# Power_Distribution_-_Rear_Camera_and_Cha.net
KiCad netlist of a schematic drawn in Altium Designer
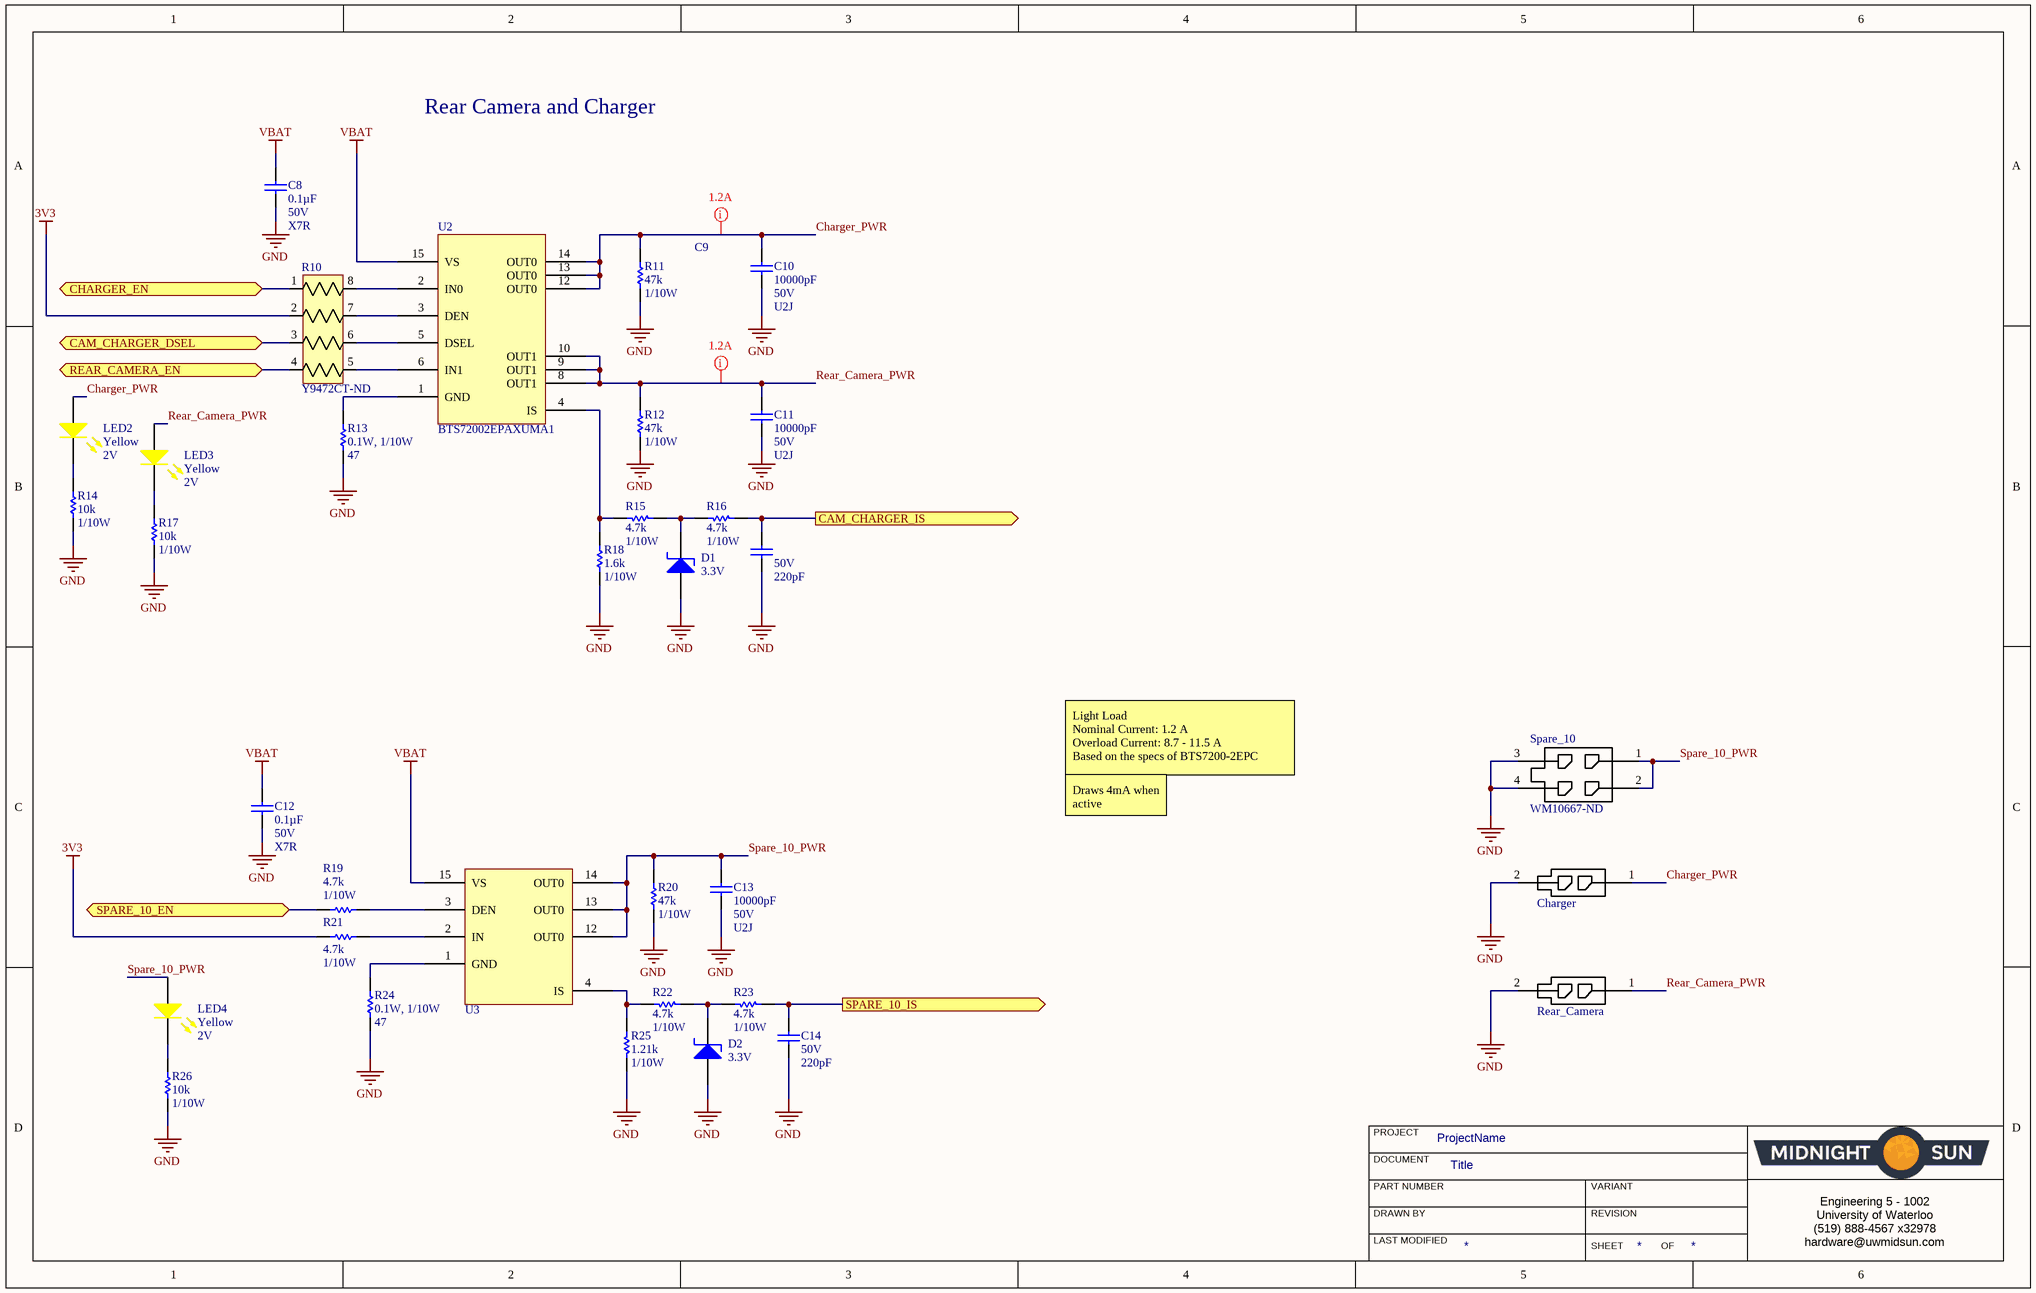
[diagram p0: Power Distribution -  Rear Camera and Charger.SchDoc]

(export (version "E")
  (design (tool "Eeschema 10.0.6"))
  (components
    (comp (ref "C8")
      (value "CAP CER 0.1UF 50V 10% X7R 0603")
      (footprint "CAP, 0603")
      (description "0.10µF ±10% 50V Ceramic Capacitor X7R 0603 (1608 Metric)")
      (fields
        (field (name "TOLERANCE") "±10%")
        (field (name "CAPACITANCE") "0.1µF")
        (field (name "VOLTAGE") "50V")
        (field (name "TEMPERATURE COEFFICIENT") "X7R")
      )
      (libsource (lib "Schematic Diagrams") (part "CAP CER 0.1UF 50V 10% X7R 0603"))
    )
    (comp (ref "C9")
      (value "CAP CER 220PF 50V C0G/NP0 0603")
      (footprint "CAP, 0603")
      (description "220pF ±5% 50V Ceramic Capacitor C0G, NP0 0603 (1608 Metric)")
      (fields
        (field (name "MANUFACTURER") "KEMET")
        (field (name "TOLERANCE") "5%")
        (field (name "VOLTAGE RATING") "50V")
        (field (name "CAPACITANCE") "220pF")
      )
      (libsource (lib "Schematic Diagrams") (part "CAP CER 220PF 50V C0G/NP0 0603"))
    )
    (comp (ref "C10")
      (value "CAP CER 10nF 50V 5% X7R 0603")
      (footprint "CAP, 0603")
      (description "10000pF ±5% 50V Ceramic Capacitor U2J 0603 (1608 Metric)")
      (fields
        (field (name "TOLERANCE") "±5%")
        (field (name "CAPACITANCE") "10000pF")
        (field (name "VOLTAGE") "50V")
        (field (name "TEMPERATURE COEFFICIENT") "U2J")
      )
      (libsource (lib "Schematic Diagrams") (part "CAP CER 10nF 50V 5% X7R 0603"))
    )
    (comp (ref "C11")
      (value "CAP CER 10nF 50V 5% X7R 0603")
      (footprint "CAP, 0603")
      (description "10000pF ±5% 50V Ceramic Capacitor U2J 0603 (1608 Metric)")
      (fields
        (field (name "TOLERANCE") "±5%")
        (field (name "CAPACITANCE") "10000pF")
        (field (name "VOLTAGE") "50V")
        (field (name "TEMPERATURE COEFFICIENT") "U2J")
      )
      (libsource (lib "Schematic Diagrams") (part "CAP CER 10nF 50V 5% X7R 0603"))
    )
    (comp (ref "C12")
      (value "CAP CER 0.1UF 50V 10% X7R 0603")
      (footprint "CAP, 0603")
      (description "0.10µF ±10% 50V Ceramic Capacitor X7R 0603 (1608 Metric)")
      (fields
        (field (name "TOLERANCE") "±10%")
        (field (name "CAPACITANCE") "0.1µF")
        (field (name "VOLTAGE") "50V")
        (field (name "TEMPERATURE COEFFICIENT") "X7R")
      )
      (libsource (lib "Schematic Diagrams") (part "CAP CER 0.1UF 50V 10% X7R 0603"))
    )
    (comp (ref "C13")
      (value "CAP CER 10nF 50V 5% X7R 0603")
      (footprint "CAP, 0603")
      (description "10000pF ±5% 50V Ceramic Capacitor U2J 0603 (1608 Metric)")
      (fields
        (field (name "TOLERANCE") "±5%")
        (field (name "CAPACITANCE") "10000pF")
        (field (name "VOLTAGE") "50V")
        (field (name "TEMPERATURE COEFFICIENT") "U2J")
      )
      (libsource (lib "Schematic Diagrams") (part "CAP CER 10nF 50V 5% X7R 0603"))
    )
    (comp (ref "C14")
      (value "CAP CER 220PF 50V C0G/NP0 0603")
      (footprint "CAP, 0603")
      (description "220pF ±5% 50V Ceramic Capacitor C0G, NP0 0603 (1608 Metric)")
      (fields
        (field (name "MANUFACTURER") "KEMET")
        (field (name "TOLERANCE") "5%")
        (field (name "VOLTAGE RATING") "50V")
        (field (name "CAPACITANCE") "220pF")
      )
      (libsource (lib "Schematic Diagrams") (part "CAP CER 220PF 50V C0G/NP0 0603"))
    )
    (comp (ref "Charger")
      (value "CONN 2POS MICRO-FIT 3mm")
      (footprint "CONN, 2POS MICRO-FIT")
      (description "Connector Header Through Hole 2 position")
      (fields (field (name "MANUFACTURER") "Molex") (field (name "MANUFACTURER PART NUMBER") "43045-0227"))
      (libsource (lib "Schematic Diagrams") (part "CONN 2POS MICRO-FIT 3mm"))
    )
    (comp (ref "D1")
      (value "DIODE ZENER 3.3V 200MW SOD323")
      (footprint "sod-323")
      (description "Zener Diode 3.3V 200mW ±5% Surface Mount SOD-323")
      (fields (field (name "VOLTAGE") "3.3V"))
      (libsource (lib "Schematic Diagrams") (part "DIODE ZENER 3.3V 200MW SOD323"))
    )
    (comp (ref "D2")
      (value "DIODE ZENER 3.3V 200MW SOD323")
      (footprint "sod-323")
      (description "Zener Diode 3.3V 200mW ±5% Surface Mount SOD-323")
      (fields (field (name "VOLTAGE") "3.3V"))
      (libsource (lib "Schematic Diagrams") (part "DIODE ZENER 3.3V 200MW SOD323"))
    )
    (comp (ref "LED2")
      (value "LED YELLOW CLEAR 2.1V 0603")
      (footprint "LED_0603")
      (description "Yellow 590nm LED Indication - Discrete 2V 0603 (1608 Metric)")
      (fields
        (field (name "MANUFACTURER") "Wurth Electronics Inc.")
        (field (name "MANUFACTURER PART NUMBER") "150060YS75000")
        (field (name "COLOR") "Yellow")
        (field (name "VOLTAGE - FORWARD (VF) (TYP)") "2V")
      )
      (libsource (lib "Schematic Diagrams") (part "LED YELLOW CLEAR 2.1V 0603"))
    )
    (comp (ref "LED3")
      (value "LED YELLOW CLEAR 2.1V 0603")
      (footprint "LED_0603")
      (description "Yellow 590nm LED Indication - Discrete 2V 0603 (1608 Metric)")
      (fields
        (field (name "MANUFACTURER") "Wurth Electronics Inc.")
        (field (name "MANUFACTURER PART NUMBER") "150060YS75000")
        (field (name "COLOR") "Yellow")
        (field (name "VOLTAGE - FORWARD (VF) (TYP)") "2V")
      )
      (libsource (lib "Schematic Diagrams") (part "LED YELLOW CLEAR 2.1V 0603"))
    )
    (comp (ref "LED4")
      (value "LED YELLOW CLEAR 2.1V 0603")
      (footprint "LED_0603")
      (description "Yellow 590nm LED Indication - Discrete 2V 0603 (1608 Metric)")
      (fields
        (field (name "MANUFACTURER") "Wurth Electronics Inc.")
        (field (name "MANUFACTURER PART NUMBER") "150060YS75000")
        (field (name "COLOR") "Yellow")
        (field (name "VOLTAGE - FORWARD (VF) (TYP)") "2V")
      )
      (libsource (lib "Schematic Diagrams") (part "LED YELLOW CLEAR 2.1V 0603"))
    )
    (comp (ref "R10")
      (value "RES ARRAY 4 RES 4.7K OHM 1206")
      (footprint "RES ARRAY 4RES 1206")
      (fields (field (name "TOLERANCE") "±5%") (field (name "SUPPLIER PART NUMBER 1") "Y9472CT-ND"))
      (libsource (lib "Schematic Diagrams") (part "RES ARRAY 4 RES 4.7K OHM 1206"))
    )
    (comp (ref "R11")
      (value "RES 47K OHM 1% 1/10W 0603")
      (footprint "RES, 0603")
      (description "47 kOhms ±1% 0.1W, 1/10W Chip Resistor 0603 (1608 Metric) Automotive AEC-Q200 Thick Film")
      (fields
        (field (name "MANUFACTURER") "Panasonic")
        (field (name "MANUFACTURER PART NUMBER") "ERJ3EKF4702V")
        (field (name "RESISTANCE") "47k")
        (field (name "POWER RATING") "1/10W")
      )
      (libsource (lib "Schematic Diagrams") (part "RES 47K OHM 1% 1/10W 0603"))
    )
    (comp (ref "R12")
      (value "RES 47K OHM 1% 1/10W 0603")
      (footprint "RES, 0603")
      (description "47 kOhms ±1% 0.1W, 1/10W Chip Resistor 0603 (1608 Metric) Automotive AEC-Q200 Thick Film")
      (fields
        (field (name "MANUFACTURER") "Panasonic")
        (field (name "MANUFACTURER PART NUMBER") "ERJ3EKF4702V")
        (field (name "RESISTANCE") "47k")
        (field (name "POWER RATING") "1/10W")
      )
      (libsource (lib "Schematic Diagrams") (part "RES 47K OHM 1% 1/10W 0603"))
    )
    (comp (ref "R13")
      (value "RES SMD 47 OHM 1% 1/10W 0603")
      (footprint "RES, 0603")
      (fields
        (field (name "TOLERANCE") "±1%")
        (field (name "POWER (WATTS)") "0.1W, 1/10W")
        (field (name "VALUES") "47")
      )
      (libsource (lib "Schematic Diagrams") (part "RES SMD 47 OHM 1% 1/10W 0603"))
    )
    (comp (ref "R14")
      (value "RES 10K OHM 1% 1/10W 0603")
      (footprint "RES, 0603")
      (description "RES SMD 10K OHM 1% 1/10W 0603")
      (fields
        (field (name "TOLERANCE") "±1%")
        (field (name "RESISTANCE") "10k")
        (field (name "POWER") "1/10W")
      )
      (libsource (lib "Schematic Diagrams") (part "RES 10K OHM 1% 1/10W 0603"))
    )
    (comp (ref "R15")
      (value "RES 4.7K OHM 1% 1/10W 0603")
      (footprint "RES, 0603")
      (description "4.7k Ohm ±1% 0.1W, 1/10W Chip Resistor 0603 (1608 Metric) Moisture Resistant Thick Film")
      (fields
        (field (name "TOLERANCE") "±1%")
        (field (name "RESISTANCE (OHMS)") "4.7k")
        (field (name "POWER (WATTS)") "1/10W")
      )
      (libsource (lib "Schematic Diagrams") (part "RES 4.7K OHM 1% 1/10W 0603"))
    )
    (comp (ref "R16")
      (value "RES 4.7K OHM 1% 1/10W 0603")
      (footprint "RES, 0603")
      (description "4.7k Ohm ±1% 0.1W, 1/10W Chip Resistor 0603 (1608 Metric) Moisture Resistant Thick Film")
      (fields
        (field (name "TOLERANCE") "±1%")
        (field (name "RESISTANCE (OHMS)") "4.7k")
        (field (name "POWER (WATTS)") "1/10W")
      )
      (libsource (lib "Schematic Diagrams") (part "RES 4.7K OHM 1% 1/10W 0603"))
    )
    (comp (ref "R17")
      (value "RES 10K OHM 1% 1/10W 0603")
      (footprint "RES, 0603")
      (description "RES SMD 10K OHM 1% 1/10W 0603")
      (fields
        (field (name "TOLERANCE") "±1%")
        (field (name "RESISTANCE") "10k")
        (field (name "POWER") "1/10W")
      )
      (libsource (lib "Schematic Diagrams") (part "RES 10K OHM 1% 1/10W 0603"))
    )
    (comp (ref "R18")
      (value "RES 1.6K OHM 1% 1/10W 0603")
      (footprint "RES, 0603")
      (description "1.6 kOhms ±1% 0.1W, 1/10W Chip Resistor 0603 (1608 Metric) Moisture Resistant Thick Film")
      (fields
        (field (name "MANUFACTURER") "Yageo")
        (field (name "MANUFACTURER PART NUMBER") "RC0603FR-071K6L")
        (field (name "RESISTANCE") "1.6k")
        (field (name "POWER RATING") "1/10W")
      )
      (libsource (lib "Schematic Diagrams") (part "RES 1.6K OHM 1% 1/10W 0603"))
    )
    (comp (ref "R19")
      (value "RES 4.7K OHM 1% 1/10W 0603")
      (footprint "RES, 0603")
      (description "4.7k Ohm ±1% 0.1W, 1/10W Chip Resistor 0603 (1608 Metric) Moisture Resistant Thick Film")
      (fields
        (field (name "TOLERANCE") "±1%")
        (field (name "RESISTANCE (OHMS)") "4.7k")
        (field (name "POWER (WATTS)") "1/10W")
      )
      (libsource (lib "Schematic Diagrams") (part "RES 4.7K OHM 1% 1/10W 0603"))
    )
    (comp (ref "R20")
      (value "RES 47K OHM 1% 1/10W 0603")
      (footprint "RES, 0603")
      (description "47 kOhms ±1% 0.1W, 1/10W Chip Resistor 0603 (1608 Metric) Automotive AEC-Q200 Thick Film")
      (fields
        (field (name "MANUFACTURER") "Panasonic")
        (field (name "MANUFACTURER PART NUMBER") "ERJ3EKF4702V")
        (field (name "RESISTANCE") "47k")
        (field (name "POWER RATING") "1/10W")
      )
      (libsource (lib "Schematic Diagrams") (part "RES 47K OHM 1% 1/10W 0603"))
    )
    (comp (ref "R21")
      (value "RES 4.7K OHM 1% 1/10W 0603")
      (footprint "RES, 0603")
      (description "4.7k Ohm ±1% 0.1W, 1/10W Chip Resistor 0603 (1608 Metric) Moisture Resistant Thick Film")
      (fields
        (field (name "TOLERANCE") "±1%")
        (field (name "RESISTANCE (OHMS)") "4.7k")
        (field (name "POWER (WATTS)") "1/10W")
      )
      (libsource (lib "Schematic Diagrams") (part "RES 4.7K OHM 1% 1/10W 0603"))
    )
    (comp (ref "R22")
      (value "RES 4.7K OHM 1% 1/10W 0603")
      (footprint "RES, 0603")
      (description "4.7k Ohm ±1% 0.1W, 1/10W Chip Resistor 0603 (1608 Metric) Moisture Resistant Thick Film")
      (fields
        (field (name "TOLERANCE") "±1%")
        (field (name "RESISTANCE (OHMS)") "4.7k")
        (field (name "POWER (WATTS)") "1/10W")
      )
      (libsource (lib "Schematic Diagrams") (part "RES 4.7K OHM 1% 1/10W 0603"))
    )
    (comp (ref "R23")
      (value "RES 4.7K OHM 1% 1/10W 0603")
      (footprint "RES, 0603")
      (description "4.7k Ohm ±1% 0.1W, 1/10W Chip Resistor 0603 (1608 Metric) Moisture Resistant Thick Film")
      (fields
        (field (name "TOLERANCE") "±1%")
        (field (name "RESISTANCE (OHMS)") "4.7k")
        (field (name "POWER (WATTS)") "1/10W")
      )
      (libsource (lib "Schematic Diagrams") (part "RES 4.7K OHM 1% 1/10W 0603"))
    )
    (comp (ref "R24")
      (value "RES SMD 47 OHM 1% 1/10W 0603")
      (footprint "RES, 0603")
      (fields
        (field (name "TOLERANCE") "±1%")
        (field (name "POWER (WATTS)") "0.1W, 1/10W")
        (field (name "VALUES") "47")
      )
      (libsource (lib "Schematic Diagrams") (part "RES SMD 47 OHM 1% 1/10W 0603"))
    )
    (comp (ref "R25")
      (value "RES 1.21K OHM 1% 1/10W 0603")
      (footprint "RES, 0603")
      (description "1.21k Ohm ±1% 0.1W, 1/10W Chip Resistor 0603 (1608 Metric) Moisture Resistant Thick Film")
      (fields
        (field (name "TOLERANCE") "±1%")
        (field (name "RESISTANCE") "1.21k")
        (field (name "POWER") "1/10W")
      )
      (libsource (lib "Schematic Diagrams") (part "RES 1.21K OHM 1% 1/10W 0603"))
    )
    (comp (ref "R26")
      (value "RES 10K OHM 1% 1/10W 0603")
      (footprint "RES, 0603")
      (description "RES SMD 10K OHM 1% 1/10W 0603")
      (fields
        (field (name "TOLERANCE") "±1%")
        (field (name "RESISTANCE") "10k")
        (field (name "POWER") "1/10W")
      )
      (libsource (lib "Schematic Diagrams") (part "RES 10K OHM 1% 1/10W 0603"))
    )
    (comp (ref "Rear_Camera")
      (value "CONN 2POS MICRO-FIT 3mm")
      (footprint "CONN, 2POS MICRO-FIT")
      (description "Connector Header Through Hole 2 position")
      (fields (field (name "MANUFACTURER") "Molex") (field (name "MANUFACTURER PART NUMBER") "43045-0227"))
      (libsource (lib "Schematic Diagrams") (part "CONN 2POS MICRO-FIT 3mm"))
    )
    (comp (ref "Spare_10")
      (value "CONN 4POS MICRO-FIT 3mm")
      (footprint "CONN 4POS MICROFIT (2x2)")
      (fields
        (field (name "MANUFACTURER") "Molex, LLC")
        (field (name "MANUFACTURER PART NUMBER") "430450427")
        (field (name "SUPPLIER PART NUMBER 1") "WM10667-ND")
      )
      (libsource (lib "Schematic Diagrams") (part "CONN 4POS MICRO-FIT 3mm"))
    )
    (comp (ref "U2")
      (value "IC LOAD SWITCH BTS7200-2EPA PG-TSDSO-14_1")
      (footprint "IC LOAD SWITCH PG-TSDSO-14-22")
      (description "Power Switch/Driver 1:1 N-Channel 1.2A PG-TSDSO-14-22")
      (fields
        (field (name "MANUFACTURER") "Infineon")
        (field (name "MANUFACTURER PART NUMBER") "BTS72002EPAXUMA1")
      )
      (libsource (lib "Schematic Diagrams") (part "IC LOAD SWITCH BTS7200-2EPA PG-TSDSO-14_1"))
    )
    (comp (ref "U3")
      (value "IC LOAD SWITCH BTS70401EPA PG-TSDSO-14-22")
      (footprint "IC LOAD SWITCH PG-TSDSO-14-22")
      (description "Power Switch/Driver 1:1 N-Channel 4.5A PG-TSDSO-14-22")
      (fields
        (field (name "MANUFACTURER") "Infineon")
        (field (name "MANUFACTURER PART NUMBER") "BTS70401EPAXUMA1")
      )
      (libsource (lib "Schematic Diagrams") (part "IC LOAD SWITCH BTS70401EPA PG-TSDSO-14-22"))
    )
  )
  (nets
    (net (code "1") (name "/CAM_CHARGER_DSEL") (class "Default")
      (node (ref "R10") (pin "3") (pinfunction "3_3") (pintype "passive"))
    )
    (net (code "2") (name "/CAM_CHARGER_IS") (class "Default")
      (node (ref "C9") (pin "1") (pinfunction "1_1") (pintype "passive"))
      (node (ref "R16") (pin "1") (pinfunction "1_1") (pintype "passive"))
    )
    (net (code "3") (name "/CHARGER_EN") (class "Default")
      (node (ref "R10") (pin "1") (pinfunction "1_1") (pintype "passive"))
    )
    (net (code "4") (name "/Charger_PWR") (class "Default")
      (node (ref "C10") (pin "1") (pinfunction "1_1") (pintype "passive"))
      (node (ref "Charger") (pin "1") (pinfunction "1_1") (pintype "passive"))
      (node (ref "LED2") (pin "1") (pinfunction "A_1") (pintype "passive"))
      (node (ref "R11") (pin "1") (pinfunction "1_1") (pintype "passive"))
      (node (ref "U2") (pin "12") (pinfunction "OUT0_12") (pintype "passive"))
      (node (ref "U2") (pin "13") (pinfunction "OUT0_13") (pintype "passive"))
      (node (ref "U2") (pin "14") (pinfunction "OUT0_14") (pintype "passive"))
    )
    (net (code "5") (name "/REAR_CAMERA_EN") (class "Default")
      (node (ref "R10") (pin "4") (pinfunction "4_4") (pintype "passive"))
    )
    (net (code "6") (name "/Rear_Camera_PWR") (class "Default")
      (node (ref "C11") (pin "1") (pinfunction "1_1") (pintype "passive"))
      (node (ref "LED3") (pin "1") (pinfunction "A_1") (pintype "passive"))
      (node (ref "R12") (pin "1") (pinfunction "1_1") (pintype "passive"))
      (node (ref "Rear_Camera") (pin "1") (pinfunction "1_1") (pintype "passive"))
      (node (ref "U2") (pin "10") (pinfunction "OUT1_10") (pintype "passive"))
      (node (ref "U2") (pin "8") (pinfunction "OUT1_8") (pintype "passive"))
      (node (ref "U2") (pin "9") (pinfunction "OUT1_9") (pintype "passive"))
    )
    (net (code "7") (name "/SPARE_10_EN") (class "Default")
      (node (ref "R19") (pin "1") (pinfunction "1_1") (pintype "passive"))
    )
    (net (code "8") (name "/SPARE_10_IS") (class "Default")
      (node (ref "C14") (pin "1") (pinfunction "1_1") (pintype "passive"))
      (node (ref "R23") (pin "1") (pinfunction "1_1") (pintype "passive"))
    )
    (net (code "9") (name "/Spare_10_PWR") (class "Default")
      (node (ref "C13") (pin "1") (pinfunction "1_1") (pintype "passive"))
      (node (ref "LED4") (pin "1") (pinfunction "A_1") (pintype "passive"))
      (node (ref "R20") (pin "1") (pinfunction "1_1") (pintype "passive"))
      (node (ref "Spare_10") (pin "1") (pinfunction "1_1") (pintype "passive"))
      (node (ref "Spare_10") (pin "2") (pinfunction "2_2") (pintype "passive"))
      (node (ref "U3") (pin "12") (pinfunction "OUT0_12") (pintype "passive"))
      (node (ref "U3") (pin "13") (pinfunction "OUT0_13") (pintype "passive"))
      (node (ref "U3") (pin "14") (pinfunction "OUT0_14") (pintype "passive"))
    )
    (net (code "10") (name "3V3") (class "Default")
      (node (ref "R10") (pin "2") (pinfunction "2_2") (pintype "passive"))
      (node (ref "R21") (pin "1") (pinfunction "1_1") (pintype "passive"))
    )
    (net (code "11") (name "GND") (class "Default")
      (node (ref "C10") (pin "2") (pinfunction "2_2") (pintype "passive"))
      (node (ref "C11") (pin "2") (pinfunction "2_2") (pintype "passive"))
      (node (ref "C12") (pin "2") (pinfunction "2_2") (pintype "passive"))
      (node (ref "C13") (pin "2") (pinfunction "2_2") (pintype "passive"))
      (node (ref "C14") (pin "2") (pinfunction "2_2") (pintype "passive"))
      (node (ref "C8") (pin "2") (pinfunction "2_2") (pintype "passive"))
      (node (ref "C9") (pin "2") (pinfunction "2_2") (pintype "passive"))
      (node (ref "Charger") (pin "2") (pinfunction "2_2") (pintype "passive"))
      (node (ref "D1") (pin "1") (pinfunction "A_1") (pintype "passive"))
      (node (ref "D2") (pin "1") (pinfunction "A_1") (pintype "passive"))
      (node (ref "R11") (pin "2") (pinfunction "2_2") (pintype "passive"))
      (node (ref "R12") (pin "2") (pinfunction "2_2") (pintype "passive"))
      (node (ref "R13") (pin "2") (pinfunction "2_2") (pintype "passive"))
      (node (ref "R14") (pin "2") (pinfunction "2_2") (pintype "passive"))
      (node (ref "R17") (pin "2") (pinfunction "2_2") (pintype "passive"))
      (node (ref "R18") (pin "2") (pinfunction "2_2") (pintype "passive"))
      (node (ref "R20") (pin "2") (pinfunction "2_2") (pintype "passive"))
      (node (ref "R24") (pin "2") (pinfunction "2_2") (pintype "passive"))
      (node (ref "R25") (pin "2") (pinfunction "2_2") (pintype "passive"))
      (node (ref "R26") (pin "2") (pinfunction "2_2") (pintype "passive"))
      (node (ref "Rear_Camera") (pin "2") (pinfunction "2_2") (pintype "passive"))
      (node (ref "Spare_10") (pin "3") (pinfunction "3_3") (pintype "passive"))
      (node (ref "Spare_10") (pin "4") (pinfunction "4_4") (pintype "passive"))
    )
    (net (code "12") (name "Net-(D1-K)") (class "Default")
      (node (ref "D1") (pin "2") (pinfunction "K_2") (pintype "passive"))
      (node (ref "R15") (pin "1") (pinfunction "1_1") (pintype "passive"))
      (node (ref "R16") (pin "2") (pinfunction "2_2") (pintype "passive"))
    )
    (net (code "13") (name "Net-(D2-K)") (class "Default")
      (node (ref "D2") (pin "2") (pinfunction "K_2") (pintype "passive"))
      (node (ref "R22") (pin "1") (pinfunction "1_1") (pintype "passive"))
      (node (ref "R23") (pin "2") (pinfunction "2_2") (pintype "passive"))
    )
    (net (code "14") (name "Net-(LED2-K)") (class "Default")
      (node (ref "LED2") (pin "2") (pinfunction "K_2") (pintype "passive"))
      (node (ref "R14") (pin "1") (pinfunction "1_1") (pintype "passive"))
    )
    (net (code "15") (name "Net-(LED3-K)") (class "Default")
      (node (ref "LED3") (pin "2") (pinfunction "K_2") (pintype "passive"))
      (node (ref "R17") (pin "1") (pinfunction "1_1") (pintype "passive"))
    )
    (net (code "16") (name "Net-(LED4-K)") (class "Default")
      (node (ref "LED4") (pin "2") (pinfunction "K_2") (pintype "passive"))
      (node (ref "R26") (pin "1") (pinfunction "1_1") (pintype "passive"))
    )
    (net (code "17") (name "Net-(U2-DEN)") (class "Default")
      (node (ref "R10") (pin "7") (pinfunction "7_7") (pintype "passive"))
      (node (ref "U2") (pin "3") (pinfunction "DEN_3") (pintype "passive"))
    )
    (net (code "18") (name "Net-(U2-DSEL)") (class "Default")
      (node (ref "R10") (pin "6") (pinfunction "6_6") (pintype "passive"))
      (node (ref "U2") (pin "5") (pinfunction "DSEL_5") (pintype "passive"))
    )
    (net (code "19") (name "Net-(U2-GND)") (class "Default")
      (node (ref "R13") (pin "1") (pinfunction "1_1") (pintype "passive"))
      (node (ref "U2") (pin "1") (pinfunction "GND_1") (pintype "passive"))
    )
    (net (code "20") (name "Net-(U2-IN0)") (class "Default")
      (node (ref "R10") (pin "8") (pinfunction "8_8") (pintype "passive"))
      (node (ref "U2") (pin "2") (pinfunction "IN0_2") (pintype "passive"))
    )
    (net (code "21") (name "Net-(U2-IN1)") (class "Default")
      (node (ref "R10") (pin "5") (pinfunction "5_5") (pintype "passive"))
      (node (ref "U2") (pin "6") (pinfunction "IN1_6") (pintype "passive"))
    )
    (net (code "22") (name "Net-(U2-IS)") (class "Default")
      (node (ref "R15") (pin "2") (pinfunction "2_2") (pintype "passive"))
      (node (ref "R18") (pin "1") (pinfunction "1_1") (pintype "passive"))
      (node (ref "U2") (pin "4") (pinfunction "IS_4") (pintype "passive"))
    )
    (net (code "23") (name "Net-(U3-DEN)") (class "Default")
      (node (ref "R19") (pin "2") (pinfunction "2_2") (pintype "passive"))
      (node (ref "U3") (pin "3") (pinfunction "DEN_3") (pintype "passive"))
    )
    (net (code "24") (name "Net-(U3-GND)") (class "Default")
      (node (ref "R24") (pin "1") (pinfunction "1_1") (pintype "passive"))
      (node (ref "U3") (pin "1") (pinfunction "GND_1") (pintype "passive"))
    )
    (net (code "25") (name "Net-(U3-IN)") (class "Default")
      (node (ref "R21") (pin "2") (pinfunction "2_2") (pintype "passive"))
      (node (ref "U3") (pin "2") (pinfunction "IN_2") (pintype "passive"))
    )
    (net (code "26") (name "Net-(U3-IS)") (class "Default")
      (node (ref "R22") (pin "2") (pinfunction "2_2") (pintype "passive"))
      (node (ref "R25") (pin "1") (pinfunction "1_1") (pintype "passive"))
      (node (ref "U3") (pin "4") (pinfunction "IS_4") (pintype "passive"))
    )
    (net (code "27") (name "VBAT") (class "Default")
      (node (ref "C12") (pin "1") (pinfunction "1_1") (pintype "passive"))
      (node (ref "C8") (pin "1") (pinfunction "1_1") (pintype "passive"))
      (node (ref "U2") (pin "15") (pinfunction "VS_15") (pintype "passive"))
      (node (ref "U3") (pin "15") (pinfunction "VS_15") (pintype "passive"))
    )
  )
)
